# levelShifter.net
KiCad netlist of a schematic drawn in Altium Designer
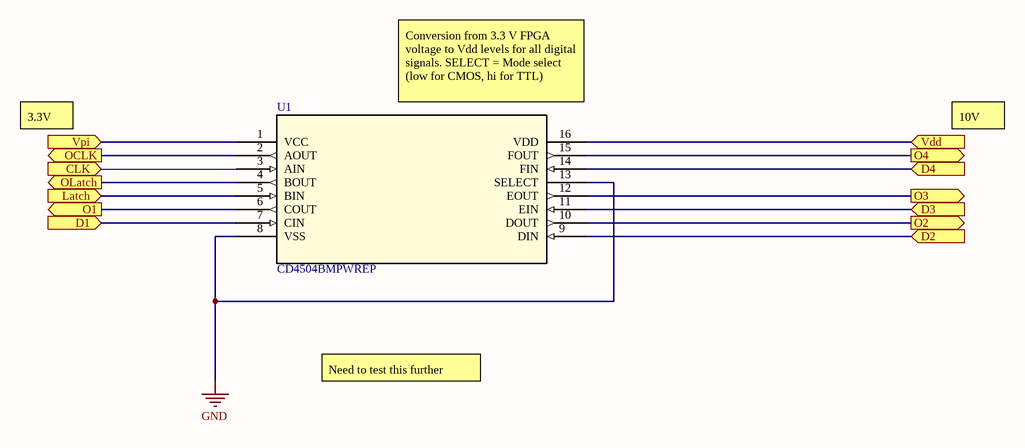
[diagram p0: levelShifter.SchDoc]

(export (version "E")
  (design (tool "Eeschema 10.0.6"))
  (components
    (comp (ref "U1")
      (value "CD4504BMPWREP")
      (footprint "PW16")
      (description "No Description Available")
      (fields (field (name "COPYRIGHT") "Copyright (C) 2022 Ultra Librarian. All rights reserved."))
      (libsource (lib "CD4504BMPWREP") (part "CD4504BMPWREP"))
    )
  )
  (nets
    (net (code "1") (name "/CLK") (class "Default")
      (node (ref "U1") (pin "3") (pinfunction "AIN_3") (pintype "input"))
    )
    (net (code "2") (name "/D1") (class "Default")
      (node (ref "U1") (pin "7") (pinfunction "CIN_7") (pintype "input"))
    )
    (net (code "3") (name "/D2") (class "Default")
      (node (ref "U1") (pin "9") (pinfunction "DIN_9") (pintype "input"))
    )
    (net (code "4") (name "/D3") (class "Default")
      (node (ref "U1") (pin "11") (pinfunction "EIN_11") (pintype "input"))
    )
    (net (code "5") (name "/D4") (class "Default")
      (node (ref "U1") (pin "14") (pinfunction "FIN_14") (pintype "input"))
    )
    (net (code "6") (name "/Latch") (class "Default")
      (node (ref "U1") (pin "5") (pinfunction "BIN_5") (pintype "input"))
    )
    (net (code "7") (name "/O1") (class "Default")
      (node (ref "U1") (pin "6") (pinfunction "COUT_6") (pintype "output"))
    )
    (net (code "8") (name "/O2") (class "Default")
      (node (ref "U1") (pin "10") (pinfunction "DOUT_10") (pintype "output"))
    )
    (net (code "9") (name "/O3") (class "Default")
      (node (ref "U1") (pin "12") (pinfunction "EOUT_12") (pintype "output"))
    )
    (net (code "10") (name "/O4") (class "Default")
      (node (ref "U1") (pin "15") (pinfunction "FOUT_15") (pintype "output"))
    )
    (net (code "11") (name "/OCLK") (class "Default")
      (node (ref "U1") (pin "2") (pinfunction "AOUT_2") (pintype "output"))
    )
    (net (code "12") (name "/OLatch") (class "Default")
      (node (ref "U1") (pin "4") (pinfunction "BOUT_4") (pintype "output"))
    )
    (net (code "13") (name "/Vdd") (class "Default")
      (node (ref "U1") (pin "16") (pinfunction "VDD_16") (pintype "power_in"))
    )
    (net (code "14") (name "/Vpi") (class "Default")
      (node (ref "U1") (pin "1") (pinfunction "VCC_1") (pintype "power_in"))
    )
    (net (code "15") (name "GND") (class "Default")
      (node (ref "U1") (pin "13") (pinfunction "SELECT_13") (pintype "passive"))
      (node (ref "U1") (pin "8") (pinfunction "VSS_8") (pintype "power_in"))
    )
  )
)
